# 3_Interface_QuadUART.net
KiCad netlist of a schematic drawn in Altium Designer
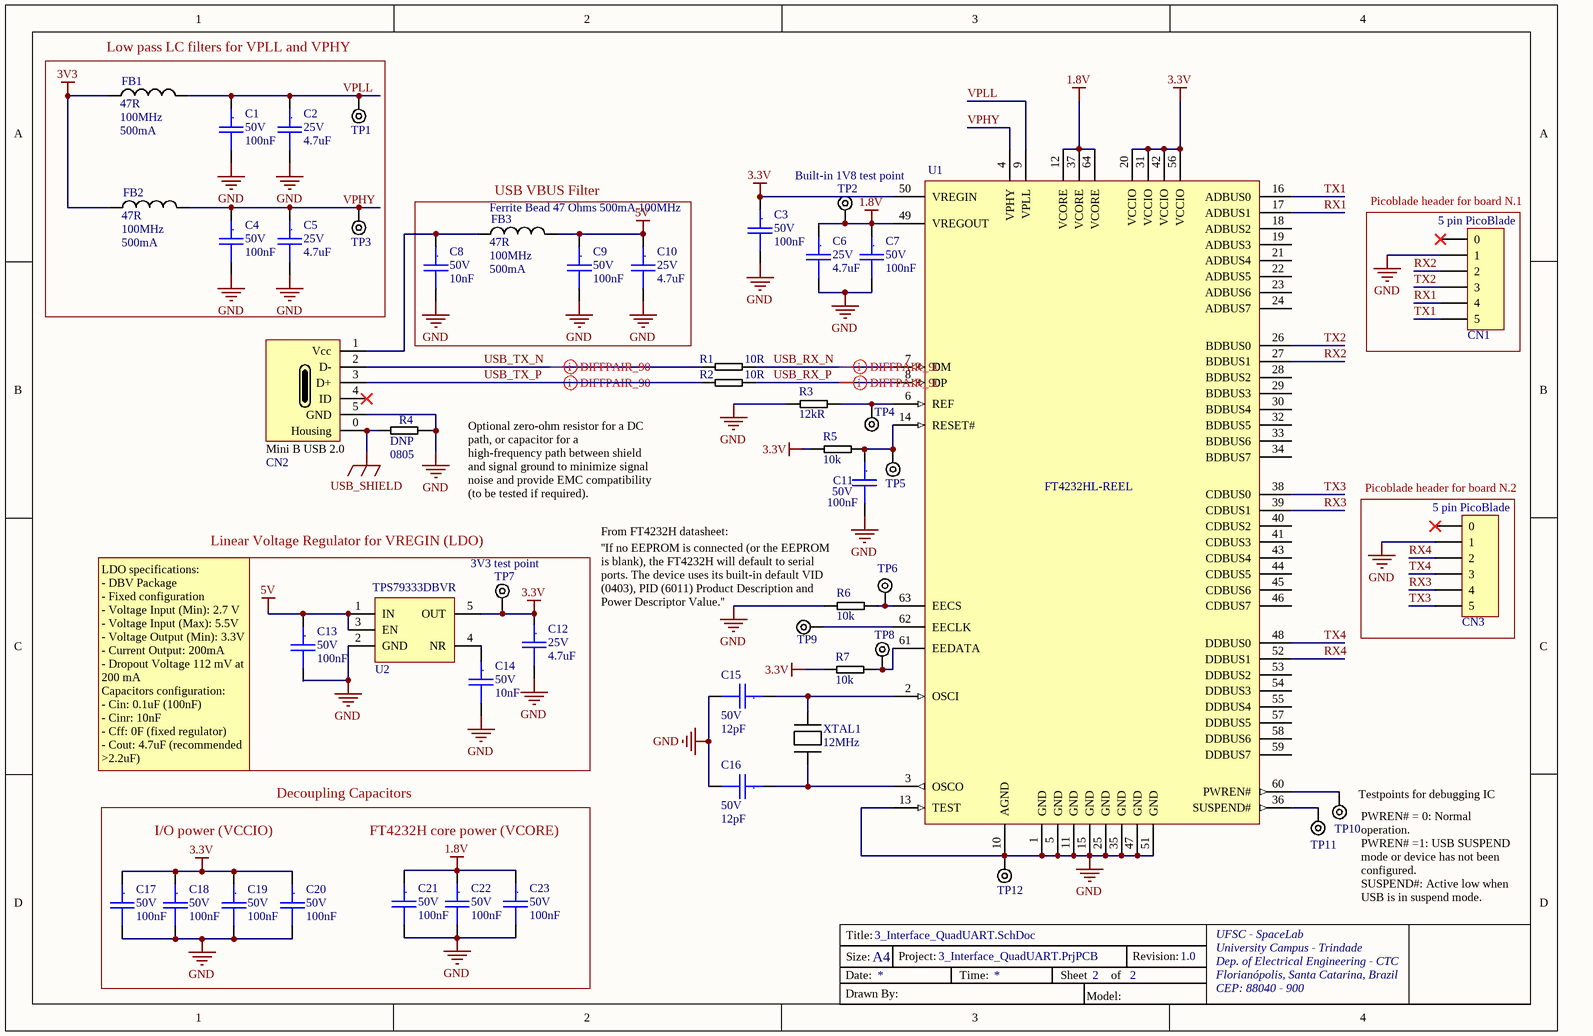
[diagram p0: 3_Interface_QuadUART.SchDoc]

(export (version "E")
  (design (tool "Eeschema 10.0.6"))
  (components
    (comp (ref "C1")
      (value "0.1 uF, 0603 (1608 metric)")
      (footprint "C0603_MD")
      (fields
        (field (name "MANUFACTURER") "TDK")
        (field (name "TOLERANCE") "10%")
        (field (name "VOLTAGE") "50V")
        (field (name "VOLTAGE RATING") "50V")
        (field (name "CAPACITANCE") "100nF")
      )
      (libsource (lib "IB_floripasat2") (part "C1608X7R1H104K080AA"))
    )
    (comp (ref "C2")
      (value "4.7 uF, 0802 (2012 metric)")
      (footprint "C0805_MD")
      (description "Ceramic Capacitor SMD Multilayer, 0805 [2012 Metric], 4.7 uF, 25 V,  10%, X7R, C Series")
      (fields
        (field (name "MANUFACTURER") "TDK")
        (field (name "TOLERANCE") "10%")
        (field (name "VOLTAGE RATING") "25V")
        (field (name "CAPACITANCE") "4.7uF")
      )
      (libsource (lib "IB_floripasat2") (part "C2012X7R1E475K125AB"))
    )
    (comp (ref "C3")
      (value "0.1 uF, 0603 (1608 metric)")
      (footprint "C0603_MD")
      (fields
        (field (name "MANUFACTURER") "TDK")
        (field (name "TOLERANCE") "10%")
        (field (name "VOLTAGE") "50V")
        (field (name "VOLTAGE RATING") "50V")
        (field (name "CAPACITANCE") "100nF")
      )
      (libsource (lib "IB_floripasat2") (part "C1608X7R1H104K080AA"))
    )
    (comp (ref "C4")
      (value "0.1 uF, 0603 (1608 metric)")
      (footprint "C0603_MD")
      (fields
        (field (name "MANUFACTURER") "TDK")
        (field (name "TOLERANCE") "10%")
        (field (name "VOLTAGE") "50V")
        (field (name "VOLTAGE RATING") "50V")
        (field (name "CAPACITANCE") "100nF")
      )
      (libsource (lib "IB_floripasat2") (part "C1608X7R1H104K080AA"))
    )
    (comp (ref "C5")
      (value "4.7 uF, 0802 (2012 metric)")
      (footprint "C0805_MD")
      (description "Ceramic Capacitor SMD Multilayer, 0805 [2012 Metric], 4.7 uF, 25 V,  10%, X7R, C Series")
      (fields
        (field (name "MANUFACTURER") "TDK")
        (field (name "TOLERANCE") "10%")
        (field (name "VOLTAGE RATING") "25V")
        (field (name "CAPACITANCE") "4.7uF")
      )
      (libsource (lib "IB_floripasat2") (part "C2012X7R1E475K125AB"))
    )
    (comp (ref "C6")
      (value "4.7 uF, 0802 (2012 metric)")
      (footprint "C0805_MD")
      (description "Ceramic Capacitor SMD Multilayer, 0805 [2012 Metric], 4.7 uF, 25 V,  10%, X7R, C Series")
      (fields
        (field (name "MANUFACTURER") "TDK")
        (field (name "TOLERANCE") "10%")
        (field (name "VOLTAGE RATING") "25V")
        (field (name "CAPACITANCE") "4.7uF")
      )
      (libsource (lib "IB_floripasat2") (part "C2012X7R1E475K125AB"))
    )
    (comp (ref "C7")
      (value "0.1 uF, 0603 (1608 metric)")
      (footprint "C0603_MD")
      (fields
        (field (name "MANUFACTURER") "TDK")
        (field (name "TOLERANCE") "10%")
        (field (name "VOLTAGE") "50V")
        (field (name "VOLTAGE RATING") "50V")
        (field (name "CAPACITANCE") "100nF")
      )
      (libsource (lib "IB_floripasat2") (part "C1608X7R1H104K080AA"))
    )
    (comp (ref "C8")
      (value "10000 pF, 0805 (2012 metric)")
      (footprint "C0805_MD")
      (fields
        (field (name "MANUFACTURER") "Kyocera AVX")
        (field (name "TOLERANCE") "10%")
        (field (name "MANUFACTURER PART NUMBER") "08055C103KAT4A")
        (field (name "VOLTAGE") "50V")
        (field (name "CAPACITANCE") "10nF")
      )
      (libsource (lib "IB_floripasat2") (part "08055C103KAT4A"))
    )
    (comp (ref "C9")
      (value "0.1 uF, 0603 (1608 metric)")
      (footprint "C0603_MD")
      (fields
        (field (name "MANUFACTURER") "TDK")
        (field (name "TOLERANCE") "10%")
        (field (name "VOLTAGE") "50V")
        (field (name "VOLTAGE RATING") "50V")
        (field (name "CAPACITANCE") "100nF")
      )
      (libsource (lib "IB_floripasat2") (part "C1608X7R1H104K080AA"))
    )
    (comp (ref "C10")
      (value "4.7 uF, 0802 (2012 metric)")
      (footprint "C0805_MD")
      (description "Ceramic Capacitor SMD Multilayer, 0805 [2012 Metric], 4.7 uF, 25 V,  10%, X7R, C Series")
      (fields
        (field (name "MANUFACTURER") "TDK")
        (field (name "TOLERANCE") "10%")
        (field (name "VOLTAGE RATING") "25V")
        (field (name "CAPACITANCE") "4.7uF")
      )
      (libsource (lib "IB_floripasat2") (part "C2012X7R1E475K125AB"))
    )
    (comp (ref "C11")
      (value "0.1 uF, 0603 (1608 metric)")
      (footprint "C0603_MD")
      (fields
        (field (name "MANUFACTURER") "TDK")
        (field (name "TOLERANCE") "10%")
        (field (name "VOLTAGE") "50V")
        (field (name "VOLTAGE RATING") "50V")
        (field (name "CAPACITANCE") "100nF")
      )
      (libsource (lib "IB_floripasat2") (part "C1608X7R1H104K080AA"))
    )
    (comp (ref "C12")
      (value "4.7 uF, 0802 (2012 metric)")
      (footprint "C0805_MD")
      (description "Ceramic Capacitor SMD Multilayer, 0805 [2012 Metric], 4.7 uF, 25 V,  10%, X7R, C Series")
      (fields
        (field (name "MANUFACTURER") "TDK")
        (field (name "TOLERANCE") "10%")
        (field (name "VOLTAGE RATING") "25V")
        (field (name "CAPACITANCE") "4.7uF")
      )
      (libsource (lib "IB_floripasat2") (part "C2012X7R1E475K125AB"))
    )
    (comp (ref "C13")
      (value "0.1 uF, 0603 (1608 metric)")
      (footprint "C0603_MD")
      (fields
        (field (name "MANUFACTURER") "TDK")
        (field (name "TOLERANCE") "10%")
        (field (name "VOLTAGE") "50V")
        (field (name "VOLTAGE RATING") "50V")
        (field (name "CAPACITANCE") "100nF")
      )
      (libsource (lib "IB_floripasat2") (part "C1608X7R1H104K080AA"))
    )
    (comp (ref "C14")
      (value "10000 pF, 0805 (2012 metric)")
      (footprint "C0805_MD")
      (fields
        (field (name "MANUFACTURER") "Kyocera AVX")
        (field (name "TOLERANCE") "10%")
        (field (name "MANUFACTURER PART NUMBER") "08055C103KAT4A")
        (field (name "VOLTAGE") "50V")
        (field (name "CAPACITANCE") "10nF")
      )
      (libsource (lib "IB_floripasat2") (part "08055C103KAT4A"))
    )
    (comp (ref "C15")
      (value "12 pF, 0603 (1608 metric)")
      (footprint "C0603_MD")
      (description "Cap Ceramic 12pF 50VDC C0G 5% SMD 0603 Paper T/R")
      (fields
        (field (name "MANUFACTURER") "Samsung")
        (field (name "MANUFACTURER PART NUMBER") "CL10C120JB8NNNC")
        (field (name "VOLTAGE") "50V")
        (field (name "CAPACITANCE") "12pF")
      )
      (libsource (lib "IB_floripasat2") (part "CL10C120JB8NNNC"))
    )
    (comp (ref "C16")
      (value "12 pF, 0603 (1608 metric)")
      (footprint "C0603_MD")
      (description "Cap Ceramic 12pF 50VDC C0G 5% SMD 0603 Paper T/R")
      (fields
        (field (name "MANUFACTURER") "Samsung")
        (field (name "MANUFACTURER PART NUMBER") "CL10C120JB8NNNC")
        (field (name "VOLTAGE") "50V")
        (field (name "CAPACITANCE") "12pF")
      )
      (libsource (lib "IB_floripasat2") (part "CL10C120JB8NNNC"))
    )
    (comp (ref "C17")
      (value "0.1 uF, 0603 (1608 metric)")
      (footprint "C0603_MD")
      (fields
        (field (name "MANUFACTURER") "TDK")
        (field (name "TOLERANCE") "10%")
        (field (name "VOLTAGE") "50V")
        (field (name "VOLTAGE RATING") "50V")
        (field (name "CAPACITANCE") "100nF")
      )
      (libsource (lib "IB_floripasat2") (part "C1608X7R1H104K080AA"))
    )
    (comp (ref "C18")
      (value "0.1 uF, 0603 (1608 metric)")
      (footprint "C0603_MD")
      (fields
        (field (name "MANUFACTURER") "TDK")
        (field (name "TOLERANCE") "10%")
        (field (name "VOLTAGE") "50V")
        (field (name "VOLTAGE RATING") "50V")
        (field (name "CAPACITANCE") "100nF")
      )
      (libsource (lib "IB_floripasat2") (part "C1608X7R1H104K080AA"))
    )
    (comp (ref "C19")
      (value "0.1 uF, 0603 (1608 metric)")
      (footprint "C0603_MD")
      (fields
        (field (name "MANUFACTURER") "TDK")
        (field (name "TOLERANCE") "10%")
        (field (name "VOLTAGE") "50V")
        (field (name "VOLTAGE RATING") "50V")
        (field (name "CAPACITANCE") "100nF")
      )
      (libsource (lib "IB_floripasat2") (part "C1608X7R1H104K080AA"))
    )
    (comp (ref "C20")
      (value "0.1 uF, 0603 (1608 metric)")
      (footprint "C0603_MD")
      (fields
        (field (name "MANUFACTURER") "TDK")
        (field (name "TOLERANCE") "10%")
        (field (name "VOLTAGE") "50V")
        (field (name "VOLTAGE RATING") "50V")
        (field (name "CAPACITANCE") "100nF")
      )
      (libsource (lib "IB_floripasat2") (part "C1608X7R1H104K080AA"))
    )
    (comp (ref "C21")
      (value "0.1 uF, 0603 (1608 metric)")
      (footprint "C0603_MD")
      (fields
        (field (name "MANUFACTURER") "TDK")
        (field (name "TOLERANCE") "10%")
        (field (name "VOLTAGE") "50V")
        (field (name "VOLTAGE RATING") "50V")
        (field (name "CAPACITANCE") "100nF")
      )
      (libsource (lib "IB_floripasat2") (part "C1608X7R1H104K080AA"))
    )
    (comp (ref "C22")
      (value "0.1 uF, 0603 (1608 metric)")
      (footprint "C0603_MD")
      (fields
        (field (name "MANUFACTURER") "TDK")
        (field (name "TOLERANCE") "10%")
        (field (name "VOLTAGE") "50V")
        (field (name "VOLTAGE RATING") "50V")
        (field (name "CAPACITANCE") "100nF")
      )
      (libsource (lib "IB_floripasat2") (part "C1608X7R1H104K080AA"))
    )
    (comp (ref "C23")
      (value "0.1 uF, 0603 (1608 metric)")
      (footprint "C0603_MD")
      (fields
        (field (name "MANUFACTURER") "TDK")
        (field (name "TOLERANCE") "10%")
        (field (name "VOLTAGE") "50V")
        (field (name "VOLTAGE RATING") "50V")
        (field (name "CAPACITANCE") "100nF")
      )
      (libsource (lib "IB_floripasat2") (part "C1608X7R1H104K080AA"))
    )
    (comp (ref "CN1")
      (value "5 pin PicoBlade")
      (footprint "PICO BLADE 0533980571")
      (description "Wire-To-Board Connector, Vertical, PicoBlade 53398 Series, Surface Mount, Header, 5, 1.25 mm")
      (fields (field (name "MANUFACTURER") "Molex") (field (name "MANUFACTURER PART NUMBER") "53398-0571"))
      (libsource (lib "IB_floripasat2") (part "53398-0571"))
    )
    (comp (ref "CN2")
      (value "Vertical mini B USB 2.0 port")
      (footprint "MINI USB B 180GRAUS WE")
      (fields
        (field (name "MANUFACTURER") "Wurth Electronics")
        (field (name "MANUFACTURER PART NUMBER") "651005136421")
      )
      (libsource (lib "IB_floripasat2") (part "651005136421"))
    )
    (comp (ref "CN3")
      (value "5 pin PicoBlade")
      (footprint "PICO BLADE 0533980571")
      (description "Wire-To-Board Connector, Vertical, PicoBlade 53398 Series, Surface Mount, Header, 5, 1.25 mm")
      (fields (field (name "MANUFACTURER") "Molex") (field (name "MANUFACTURER PART NUMBER") "53398-0571"))
      (libsource (lib "IB_floripasat2") (part "53398-0571"))
    )
    (comp (ref "FB1")
      (value "Ferrite Bead 47 Ohms 500mA 100MHz")
      (footprint "L0603")
      (description "WURTH ELEKTRONIK   742792608   FERRITE BEAD, 0.1 OHM, 0.5A, 0603")
      (fields
        (field (name "MANUFACTURER") "Wurth Electronics")
        (field (name "TOLERANCE") "25%")
        (field (name "IMPEDANCE") "47R")
        (field (name "TEST FREQUENCY") "100MHz")
        (field (name "CURRENT RATING") "500mA")
      )
      (libsource (lib "IB_floripasat2") (part "742792608"))
    )
    (comp (ref "FB2")
      (value "Ferrite Bead 47 Ohms 500mA 100MHz")
      (footprint "L0603")
      (description "WURTH ELEKTRONIK   742792608   FERRITE BEAD, 0.1 OHM, 0.5A, 0603")
      (fields
        (field (name "MANUFACTURER") "Wurth Electronics")
        (field (name "TOLERANCE") "25%")
        (field (name "IMPEDANCE") "47R")
        (field (name "TEST FREQUENCY") "100MHz")
        (field (name "CURRENT RATING") "500mA")
      )
      (libsource (lib "IB_floripasat2") (part "742792608"))
    )
    (comp (ref "FB3")
      (value "Ferrite Bead 47 Ohms 500mA 100MHz")
      (footprint "L0603")
      (description "WURTH ELEKTRONIK   742792608   FERRITE BEAD, 0.1 OHM, 0.5A, 0603")
      (fields
        (field (name "MANUFACTURER") "Wurth Electronics")
        (field (name "TOLERANCE") "25%")
        (field (name "IMPEDANCE") "47R")
        (field (name "TEST FREQUENCY") "100MHz")
        (field (name "CURRENT RATING") "500mA")
      )
      (libsource (lib "IB_floripasat2") (part "742792608"))
    )
    (comp (ref "R1")
      (value "RES 10 ohms (0603)")
      (footprint "R0603_MD")
      (description "YAGEO (PHYCOMP) - RC0603FR-0710RL - RES, THICK FILM, 10R, 1%, 0.1W, 0603")
      (fields
        (field (name "MANUFACTURER") "Yageo")
        (field (name "TOLERANCE") "1%")
        (field (name "RESISTANCE") "10R")
      )
      (libsource (lib "IB_floripasat2") (part "RC0603FR-0710RL"))
    )
    (comp (ref "R2")
      (value "RES 10 ohms (0603)")
      (footprint "R0603_MD")
      (description "YAGEO (PHYCOMP) - RC0603FR-0710RL - RES, THICK FILM, 10R, 1%, 0.1W, 0603")
      (fields
        (field (name "MANUFACTURER") "Yageo")
        (field (name "TOLERANCE") "1%")
        (field (name "RESISTANCE") "10R")
      )
      (libsource (lib "IB_floripasat2") (part "RC0603FR-0710RL"))
    )
    (comp (ref "R3")
      (value "RES 12K ohms (0805)")
      (footprint "R0805_MD")
      (description "Resistor, SMT, 0805, 12K Ohm, +/-1%, +/-100ppm, Thk Film, T/R Marked")
      (fields
        (field (name "MANUFACTURER") "Stackpole Electronics")
        (field (name "MANUFACTURER PART NUMBER") "RMCF0805FT12K0")
        (field (name "RESISTANCE") "12kR")
      )
      (libsource (lib "IB_floripasat2") (part "RMCF0805FT12K0"))
    )
    (comp (ref "R4")
      (value "DNP")
      (footprint "R0805_MD")
      (fields
        (field (name "MANUFACTURER") "Vishay")
        (field (name "TOLERANCE") "1%")
        (field (name "MANUFACTURER PART NUMBER") "CRCW08050000Z0EA")
        (field (name "CASE/PACKAGE") "0805")
      )
      (libsource (lib "IB_floripasat2") (part "CRCW08050000Z0EA"))
    )
    (comp (ref "R5")
      (value "10k")
      (footprint "R0805_MD")
      (description "RES 10.0K OHM 1/8W 1% 0805 SMD")
      (fields (field (name "MANUFACTURER") "Vishay Dale") (field (name "TOLERANCE") "1%"))
      (libsource (lib "IB_floripasat2") (part "CRCW080510K0FKEA"))
    )
    (comp (ref "R6")
      (value "10k")
      (footprint "R0805_MD")
      (description "RES 10.0K OHM 1/8W 1% 0805 SMD")
      (fields (field (name "MANUFACTURER") "Vishay Dale") (field (name "TOLERANCE") "1%"))
      (libsource (lib "IB_floripasat2") (part "CRCW080510K0FKEA"))
    )
    (comp (ref "R7")
      (value "10k")
      (footprint "R0805_MD")
      (description "RES 10.0K OHM 1/8W 1% 0805 SMD")
      (fields (field (name "MANUFACTURER") "Vishay Dale") (field (name "TOLERANCE") "1%"))
      (libsource (lib "IB_floripasat2") (part "CRCW080510K0FKEA"))
    )
    (comp (ref "TP1")
      (value "DNP")
      (footprint "TEST POINT PTH")
      (description "TEST POINT PAD")
      (libsource (lib "IB_floripasat2") (part "Test Point PTH"))
    )
    (comp (ref "TP2")
      (value "DNP")
      (footprint "TEST POINT PTH")
      (description "TEST POINT PAD")
      (libsource (lib "IB_floripasat2") (part "Test Point PTH"))
    )
    (comp (ref "TP3")
      (value "DNP")
      (footprint "TEST POINT PTH")
      (description "TEST POINT PAD")
      (libsource (lib "IB_floripasat2") (part "Test Point PTH"))
    )
    (comp (ref "TP4")
      (value "DNP")
      (footprint "TEST POINT PTH")
      (description "TEST POINT PAD")
      (libsource (lib "IB_floripasat2") (part "Test Point PTH"))
    )
    (comp (ref "TP5")
      (value "DNP")
      (footprint "TEST POINT PTH")
      (description "TEST POINT PAD")
      (libsource (lib "IB_floripasat2") (part "Test Point PTH"))
    )
    (comp (ref "TP6")
      (value "DNP")
      (footprint "TEST POINT PTH")
      (description "TEST POINT PAD")
      (libsource (lib "IB_floripasat2") (part "Test Point PTH"))
    )
    (comp (ref "TP7")
      (value "DNP")
      (footprint "TEST POINT PTH")
      (description "TEST POINT PAD")
      (libsource (lib "IB_floripasat2") (part "Test Point PTH"))
    )
    (comp (ref "TP8")
      (value "DNP")
      (footprint "TEST POINT PTH")
      (description "TEST POINT PAD")
      (libsource (lib "IB_floripasat2") (part "Test Point PTH"))
    )
    (comp (ref "TP9")
      (value "DNP")
      (footprint "TEST POINT PTH")
      (description "TEST POINT PAD")
      (libsource (lib "IB_floripasat2") (part "Test Point PTH"))
    )
    (comp (ref "TP10")
      (value "DNP")
      (footprint "TEST POINT PTH")
      (description "TEST POINT PAD")
      (libsource (lib "IB_floripasat2") (part "Test Point PTH"))
    )
    (comp (ref "TP11")
      (value "DNP")
      (footprint "TEST POINT PTH")
      (description "TEST POINT PAD")
      (libsource (lib "IB_floripasat2") (part "Test Point PTH"))
    )
    (comp (ref "TP12")
      (value "DNP")
      (footprint "TEST POINT PTH")
      (description "TEST POINT PAD")
      (libsource (lib "IB_floripasat2") (part "Test Point PTH"))
    )
    (comp (ref "U1")
      (value "FT4232HL-REEL")
      (footprint "LQFP-64")
      (description "FTDI - FT4232HL-REEL - USB-UART/MPSSE, 4232, QUAD, 64LQFP")
      (fields (field (name "MANUFACTURER") "FTDI"))
      (libsource (lib "IB_floripasat2") (part "FT4232HL-REEL"))
    )
    (comp (ref "U2")
      (value "TPS79333DBVR")
      (footprint "SOT23-5")
      (description "TEXAS INSTRUMENTS - TPS79333DBVR - IC, V REG, LINEAR, 0.2A, SOT-23-5")
      (fields (field (name "MANUFACTURER") "Texas Instruments"))
      (libsource (lib "IB_floripasat2") (part "TPS79333DBVR"))
    )
    (comp (ref "XTAL1")
      (value "12.000MHz 12pF")
      (footprint "TXC 7A Series")
      (description "Crystals 12.000MHz 30ppm 12pF -40C to 85C")
      (fields
        (field (name "MANUFACTURER") "TXC")
        (field (name "TOLERANCE") "30ppm")
        (field (name "FREQUENCY") "12MHz")
      )
      (libsource (lib "IB_floripasat2") (part "AA-12.000MAGE-T"))
    )
  )
  (nets
    (net (code "1") (name "/RX1") (class "Default")
      (node (ref "CN1") (pin "4") (pinfunction "4_4") (pintype "passive"))
      (node (ref "U1") (pin "17") (pinfunction "ADBUS1_17") (pintype "passive"))
    )
    (net (code "2") (name "/RX2") (class "Default")
      (node (ref "CN1") (pin "2") (pinfunction "2_2") (pintype "passive"))
      (node (ref "U1") (pin "27") (pinfunction "BDBUS1_27") (pintype "passive"))
    )
    (net (code "3") (name "/RX3") (class "Default")
      (node (ref "CN3") (pin "4") (pinfunction "4_4") (pintype "passive"))
      (node (ref "U1") (pin "39") (pinfunction "CDBUS1_39") (pintype "passive"))
    )
    (net (code "4") (name "/RX4") (class "Default")
      (node (ref "CN3") (pin "2") (pinfunction "2_2") (pintype "passive"))
      (node (ref "U1") (pin "52") (pinfunction "DDBUS1_52") (pintype "passive"))
    )
    (net (code "5") (name "/TX1") (class "Default")
      (node (ref "CN1") (pin "5") (pinfunction "5_5") (pintype "passive"))
      (node (ref "U1") (pin "16") (pinfunction "ADBUS0_16") (pintype "passive"))
    )
    (net (code "6") (name "/TX2") (class "Default")
      (node (ref "CN1") (pin "3") (pinfunction "3_3") (pintype "passive"))
      (node (ref "U1") (pin "26") (pinfunction "BDBUS0_26") (pintype "passive"))
    )
    (net (code "7") (name "/TX3") (class "Default")
      (node (ref "CN3") (pin "5") (pinfunction "5_5") (pintype "passive"))
      (node (ref "U1") (pin "38") (pinfunction "CDBUS0_38") (pintype "passive"))
    )
    (net (code "8") (name "/TX4") (class "Default")
      (node (ref "CN3") (pin "3") (pinfunction "3_3") (pintype "passive"))
      (node (ref "U1") (pin "48") (pinfunction "DDBUS0_48") (pintype "passive"))
    )
    (net (code "9") (name "/USB_RX_N") (class "Default")
      (node (ref "R1") (pin "2") (pinfunction "2_2") (pintype "passive"))
      (node (ref "U1") (pin "7") (pinfunction "DM_7") (pintype "bidirectional"))
    )
    (net (code "10") (name "/USB_RX_P") (class "Default")
      (node (ref "R2") (pin "2") (pinfunction "2_2") (pintype "passive"))
      (node (ref "U1") (pin "8") (pinfunction "DP_8") (pintype "bidirectional"))
    )
    (net (code "11") (name "/USB_TX_N") (class "Default")
      (node (ref "CN2") (pin "2") (pinfunction "D-_2") (pintype "passive"))
      (node (ref "R1") (pin "1") (pinfunction "1_1") (pintype "passive"))
    )
    (net (code "12") (name "/USB_TX_P") (class "Default")
      (node (ref "CN2") (pin "3") (pinfunction "D+_3") (pintype "passive"))
      (node (ref "R2") (pin "1") (pinfunction "1_1") (pintype "passive"))
    )
    (net (code "13") (name "/VPHY") (class "Default")
      (node (ref "C4") (pin "1") (pinfunction "1_1") (pintype "passive"))
      (node (ref "C5") (pin "1") (pinfunction "1_1") (pintype "passive"))
      (node (ref "FB2") (pin "2") (pinfunction "2_2") (pintype "passive"))
      (node (ref "TP3") (pin "1") (pinfunction "1_1") (pintype "passive"))
      (node (ref "U1") (pin "4") (pinfunction "VPHY_4") (pintype "power_in"))
    )
    (net (code "14") (name "/VPLL") (class "Default")
      (node (ref "C1") (pin "1") (pinfunction "1_1") (pintype "passive"))
      (node (ref "C2") (pin "1") (pinfunction "1_1") (pintype "passive"))
      (node (ref "FB1") (pin "2") (pinfunction "2_2") (pintype "passive"))
      (node (ref "TP1") (pin "1") (pinfunction "1_1") (pintype "passive"))
      (node (ref "U1") (pin "9") (pinfunction "VPLL_9") (pintype "power_in"))
    )
    (net (code "15") (name "1.8V") (class "Default")
      (node (ref "C21") (pin "1") (pinfunction "1_1") (pintype "passive"))
      (node (ref "C22") (pin "1") (pinfunction "1_1") (pintype "passive"))
      (node (ref "C23") (pin "1") (pinfunction "1_1") (pintype "passive"))
      (node (ref "C6") (pin "1") (pinfunction "1_1") (pintype "passive"))
      (node (ref "C7") (pin "1") (pinfunction "1_1") (pintype "passive"))
      (node (ref "TP2") (pin "1") (pinfunction "1_1") (pintype "passive"))
      (node (ref "U1") (pin "12") (pinfunction "VCORE_12") (pintype "power_in"))
      (node (ref "U1") (pin "37") (pinfunction "VCORE_37") (pintype "power_in"))
      (node (ref "U1") (pin "49") (pinfunction "VREGOUT_49") (pintype "passive"))
      (node (ref "U1") (pin "64") (pinfunction "VCORE_64") (pintype "power_in"))
    )
    (net (code "16") (name "3.3V") (class "Default")
      (node (ref "C12") (pin "1") (pinfunction "1_1") (pintype "passive"))
      (node (ref "C17") (pin "1") (pinfunction "1_1") (pintype "passive"))
      (node (ref "C18") (pin "1") (pinfunction "1_1") (pintype "passive"))
      (node (ref "C19") (pin "1") (pinfunction "1_1") (pintype "passive"))
      (node (ref "C20") (pin "1") (pinfunction "1_1") (pintype "passive"))
      (node (ref "C3") (pin "1") (pinfunction "1_1") (pintype "passive"))
      (node (ref "R5") (pin "1") (pinfunction "1_1") (pintype "passive"))
      (node (ref "R7") (pin "1") (pinfunction "1_1") (pintype "passive"))
      (node (ref "TP7") (pin "1") (pinfunction "1_1") (pintype "passive"))
      (node (ref "U1") (pin "20") (pinfunction "VCCIO_20") (pintype "power_in"))
      (node (ref "U1") (pin "31") (pinfunction "VCCIO_31") (pintype "power_in"))
      (node (ref "U1") (pin "42") (pinfunction "VCCIO_42") (pintype "power_in"))
      (node (ref "U1") (pin "50") (pinfunction "VREGIN_50") (pintype "passive"))
      (node (ref "U1") (pin "56") (pinfunction "VCCIO_56") (pintype "power_in"))
      (node (ref "U2") (pin "5") (pinfunction "OUT_5") (pintype "passive"))
    )
    (net (code "17") (name "3V3") (class "Default")
      (node (ref "FB1") (pin "1") (pinfunction "1_1") (pintype "passive"))
      (node (ref "FB2") (pin "1") (pinfunction "1_1") (pintype "passive"))
    )
    (net (code "18") (name "5V") (class "Default")
      (node (ref "C10") (pin "1") (pinfunction "1_1") (pintype "passive"))
      (node (ref "C13") (pin "1") (pinfunction "1_1") (pintype "passive"))
      (node (ref "C9") (pin "1") (pinfunction "1_1") (pintype "passive"))
      (node (ref "FB3") (pin "2") (pinfunction "2_2") (pintype "passive"))
      (node (ref "U2") (pin "1") (pinfunction "IN_1") (pintype "passive"))
      (node (ref "U2") (pin "3") (pinfunction "EN_3") (pintype "passive"))
    )
    (net (code "19") (name "GND") (class "Default")
      (node (ref "C1") (pin "2") (pinfunction "2_2") (pintype "passive"))
      (node (ref "C10") (pin "2") (pinfunction "2_2") (pintype "passive"))
      (node (ref "C11") (pin "2") (pinfunction "2_2") (pintype "passive"))
      (node (ref "C12") (pin "2") (pinfunction "2_2") (pintype "passive"))
      (node (ref "C13") (pin "2") (pinfunction "2_2") (pintype "passive"))
      (node (ref "C14") (pin "2") (pinfunction "2_2") (pintype "passive"))
      (node (ref "C15") (pin "2") (pinfunction "2_2") (pintype "passive"))
      (node (ref "C16") (pin "2") (pinfunction "2_2") (pintype "passive"))
      (node (ref "C17") (pin "2") (pinfunction "2_2") (pintype "passive"))
      (node (ref "C18") (pin "2") (pinfunction "2_2") (pintype "passive"))
      (node (ref "C19") (pin "2") (pinfunction "2_2") (pintype "passive"))
      (node (ref "C2") (pin "2") (pinfunction "2_2") (pintype "passive"))
      (node (ref "C20") (pin "2") (pinfunction "2_2") (pintype "passive"))
      (node (ref "C21") (pin "2") (pinfunction "2_2") (pintype "passive"))
      (node (ref "C22") (pin "2") (pinfunction "2_2") (pintype "passive"))
      (node (ref "C23") (pin "2") (pinfunction "2_2") (pintype "passive"))
      (node (ref "C3") (pin "2") (pinfunction "2_2") (pintype "passive"))
      (node (ref "C4") (pin "2") (pinfunction "2_2") (pintype "passive"))
      (node (ref "C5") (pin "2") (pinfunction "2_2") (pintype "passive"))
      (node (ref "C6") (pin "2") (pinfunction "2_2") (pintype "passive"))
      (node (ref "C7") (pin "2") (pinfunction "2_2") (pintype "passive"))
      (node (ref "C8") (pin "2") (pinfunction "2_2") (pintype "passive"))
      (node (ref "C9") (pin "2") (pinfunction "2_2") (pintype "passive"))
      (node (ref "CN1") (pin "1") (pinfunction "1_1") (pintype "passive"))
      (node (ref "CN2") (pin "5") (pinfunction "GND_5") (pintype "passive"))
      (node (ref "CN3") (pin "1") (pinfunction "1_1") (pintype "passive"))
      (node (ref "R3") (pin "1") (pinfunction "1_1") (pintype "passive"))
      (node (ref "R4") (pin "2") (pinfunction "2_2") (pintype "passive"))
      (node (ref "R6") (pin "1") (pinfunction "1_1") (pintype "passive"))
      (node (ref "TP12") (pin "1") (pinfunction "1_1") (pintype "passive"))
      (node (ref "U1") (pin "1") (pinfunction "GND_1") (pintype "passive"))
      (node (ref "U1") (pin "10") (pinfunction "AGND_10") (pintype "passive"))
      (node (ref "U1") (pin "11") (pinfunction "GND_11") (pintype "passive"))
      (node (ref "U1") (pin "13") (pinfunction "TEST_13") (pintype "input"))
      (node (ref "U1") (pin "15") (pinfunction "GND_15") (pintype "passive"))
      (node (ref "U1") (pin "25") (pinfunction "GND_25") (pintype "passive"))
      (node (ref "U1") (pin "35") (pinfunction "GND_35") (pintype "passive"))
      (node (ref "U1") (pin "47") (pinfunction "GND_47") (pintype "passive"))
      (node (ref "U1") (pin "5") (pinfunction "GND_5") (pintype "passive"))
      (node (ref "U1") (pin "51") (pinfunction "GND_51") (pintype "passive"))
      (node (ref "U2") (pin "2") (pinfunction "GND_2") (pintype "passive"))
    )
    (net (code "20") (name "Net-(CN2-Vcc)") (class "Default")
      (node (ref "C8") (pin "1") (pinfunction "1_1") (pintype "passive"))
      (node (ref "CN2") (pin "1") (pinfunction "Vcc_1") (pintype "passive"))
      (node (ref "FB3") (pin "1") (pinfunction "1_1") (pintype "passive"))
    )
    (net (code "21") (name "Net-(U1-EECLK)") (class "Default")
      (node (ref "TP9") (pin "1") (pinfunction "1_1") (pintype "passive"))
      (node (ref "U1") (pin "62") (pinfunction "EECLK_62") (pintype "passive"))
    )
    (net (code "22") (name "Net-(U1-EECS)") (class "Default")
      (node (ref "R6") (pin "2") (pinfunction "2_2") (pintype "passive"))
      (node (ref "TP6") (pin "1") (pinfunction "1_1") (pintype "passive"))
      (node (ref "U1") (pin "63") (pinfunction "EECS_63") (pintype "passive"))
    )
    (net (code "23") (name "Net-(U1-EEDATA)") (class "Default")
      (node (ref "R7") (pin "2") (pinfunction "2_2") (pintype "passive"))
      (node (ref "TP8") (pin "1") (pinfunction "1_1") (pintype "passive"))
      (node (ref "U1") (pin "61") (pinfunction "EEDATA_61") (pintype "passive"))
    )
    (net (code "24") (name "Net-(U1-OSCI)") (class "Default")
      (node (ref "C15") (pin "1") (pinfunction "1_1") (pintype "passive"))
      (node (ref "U1") (pin "2") (pinfunction "OSCI_2") (pintype "input"))
      (node (ref "XTAL1") (pin "1") (pinfunction "1_1") (pintype "passive"))
    )
    (net (code "25") (name "Net-(U1-OSCO)") (class "Default")
      (node (ref "C16") (pin "1") (pinfunction "1_1") (pintype "passive"))
      (node (ref "U1") (pin "3") (pinfunction "OSCO_3") (pintype "output"))
      (node (ref "XTAL1") (pin "2") (pinfunction "2_2") (pintype "passive"))
    )
    (net (code "26") (name "Net-(U1-PWREN#)") (class "Default")
      (node (ref "TP10") (pin "1") (pinfunction "1_1") (pintype "passive"))
      (node (ref "U1") (pin "60") (pinfunction "PWREN#_60") (pintype "output"))
    )
    (net (code "27") (name "Net-(U1-REF)") (class "Default")
      (node (ref "R3") (pin "2") (pinfunction "2_2") (pintype "passive"))
      (node (ref "TP4") (pin "1") (pinfunction "1_1") (pintype "passive"))
      (node (ref "U1") (pin "6") (pinfunction "REF_6") (pintype "input"))
    )
    (net (code "28") (name "Net-(U1-RESET#)") (class "Default")
      (node (ref "C11") (pin "1") (pinfunction "1_1") (pintype "passive"))
      (node (ref "R5") (pin "2") (pinfunction "2_2") (pintype "passive"))
      (node (ref "TP5") (pin "1") (pinfunction "1_1") (pintype "passive"))
      (node (ref "U1") (pin "14") (pinfunction "RESET#_14") (pintype "input"))
    )
    (net (code "29") (name "Net-(U1-SUSPEND#)") (class "Default")
      (node (ref "TP11") (pin "1") (pinfunction "1_1") (pintype "passive"))
      (node (ref "U1") (pin "36") (pinfunction "SUSPEND#_36") (pintype "output"))
    )
    (net (code "30") (name "Net-(U2-NR)") (class "Default")
      (node (ref "C14") (pin "1") (pinfunction "1_1") (pintype "passive"))
      (node (ref "U2") (pin "4") (pinfunction "NR_4") (pintype "passive"))
    )
    (net (code "31") (name "USB_SHIELD") (class "Default")
      (node (ref "CN2") (pin "0") (pinfunction "Housing_0") (pintype "passive"))
      (node (ref "R4") (pin "1") (pinfunction "1_1") (pintype "passive"))
    )
    (net (code "32") (name "unconnected-(CN1-Pad0)") (class "Default")
      (node (ref "CN1") (pin "0") (pinfunction "0_0") (pintype "passive+no_connect"))
    )
    (net (code "33") (name "unconnected-(CN2-ID-Pad4)") (class "Default")
      (node (ref "CN2") (pin "4") (pinfunction "ID_4") (pintype "passive+no_connect"))
    )
    (net (code "34") (name "unconnected-(CN3-Pad0)") (class "Default")
      (node (ref "CN3") (pin "0") (pinfunction "0_0") (pintype "passive+no_connect"))
    )
    (net (code "35") (name "unconnected-(U1-ADBUS2-Pad18)") (class "Default")
      (node (ref "U1") (pin "18") (pinfunction "ADBUS2_18") (pintype "passive"))
    )
    (net (code "36") (name "unconnected-(U1-ADBUS3-Pad19)") (class "Default")
      (node (ref "U1") (pin "19") (pinfunction "ADBUS3_19") (pintype "passive"))
    )
    (net (code "37") (name "unconnected-(U1-ADBUS4-Pad21)") (class "Default")
      (node (ref "U1") (pin "21") (pinfunction "ADBUS4_21") (pintype "passive"))
    )
    (net (code "38") (name "unconnected-(U1-ADBUS5-Pad22)") (class "Default")
      (node (ref "U1") (pin "22") (pinfunction "ADBUS5_22") (pintype "passive"))
    )
    (net (code "39") (name "unconnected-(U1-ADBUS6-Pad23)") (class "Default")
      (node (ref "U1") (pin "23") (pinfunction "ADBUS6_23") (pintype "passive"))
    )
    (net (code "40") (name "unconnected-(U1-ADBUS7-Pad24)") (class "Default")
      (node (ref "U1") (pin "24") (pinfunction "ADBUS7_24") (pintype "passive"))
    )
    (net (code "41") (name "unconnected-(U1-BDBUS2-Pad28)") (class "Default")
      (node (ref "U1") (pin "28") (pinfunction "BDBUS2_28") (pintype "passive"))
    )
    (net (code "42") (name "unconnected-(U1-BDBUS3-Pad29)") (class "Default")
      (node (ref "U1") (pin "29") (pinfunction "BDBUS3_29") (pintype "passive"))
    )
    (net (code "43") (name "unconnected-(U1-BDBUS4-Pad30)") (class "Default")
      (node (ref "U1") (pin "30") (pinfunction "BDBUS4_30") (pintype "passive"))
    )
    (net (code "44") (name "unconnected-(U1-BDBUS5-Pad32)") (class "Default")
      (node (ref "U1") (pin "32") (pinfunction "BDBUS5_32") (pintype "passive"))
    )
    (net (code "45") (name "unconnected-(U1-BDBUS6-Pad33)") (class "Default")
      (node (ref "U1") (pin "33") (pinfunction "BDBUS6_33") (pintype "passive"))
    )
    (net (code "46") (name "unconnected-(U1-BDBUS7-Pad34)") (class "Default")
      (node (ref "U1") (pin "34") (pinfunction "BDBUS7_34") (pintype "passive"))
    )
    (net (code "47") (name "unconnected-(U1-CDBUS2-Pad40)") (class "Default")
      (node (ref "U1") (pin "40") (pinfunction "CDBUS2_40") (pintype "passive"))
    )
    (net (code "48") (name "unconnected-(U1-CDBUS3-Pad41)") (class "Default")
      (node (ref "U1") (pin "41") (pinfunction "CDBUS3_41") (pintype "passive"))
    )
    (net (code "49") (name "unconnected-(U1-CDBUS4-Pad43)") (class "Default")
      (node (ref "U1") (pin "43") (pinfunction "CDBUS4_43") (pintype "passive"))
    )
    (net (code "50") (name "unconnected-(U1-CDBUS5-Pad44)") (class "Default")
      (node (ref "U1") (pin "44") (pinfunction "CDBUS5_44") (pintype "passive"))
    )
    (net (code "51") (name "unconnected-(U1-CDBUS6-Pad45)") (class "Default")
      (node (ref "U1") (pin "45") (pinfunction "CDBUS6_45") (pintype "passive"))
    )
    (net (code "52") (name "unconnected-(U1-CDBUS7-Pad46)") (class "Default")
      (node (ref "U1") (pin "46") (pinfunction "CDBUS7_46") (pintype "passive"))
    )
    (net (code "53") (name "unconnected-(U1-DDBUS2-Pad53)") (class "Default")
      (node (ref "U1") (pin "53") (pinfunction "DDBUS2_53") (pintype "passive"))
    )
    (net (code "54") (name "unconnected-(U1-DDBUS3-Pad54)") (class "Default")
      (node (ref "U1") (pin "54") (pinfunction "DDBUS3_54") (pintype "passive"))
    )
    (net (code "55") (name "unconnected-(U1-DDBUS4-Pad55)") (class "Default")
      (node (ref "U1") (pin "55") (pinfunction "DDBUS4_55") (pintype "passive"))
    )
    (net (code "56") (name "unconnected-(U1-DDBUS5-Pad57)") (class "Default")
      (node (ref "U1") (pin "57") (pinfunction "DDBUS5_57") (pintype "passive"))
    )
    (net (code "57") (name "unconnected-(U1-DDBUS6-Pad58)") (class "Default")
      (node (ref "U1") (pin "58") (pinfunction "DDBUS6_58") (pintype "passive"))
    )
    (net (code "58") (name "unconnected-(U1-DDBUS7-Pad59)") (class "Default")
      (node (ref "U1") (pin "59") (pinfunction "DDBUS7_59") (pintype "passive"))
    )
  )
)
